# central.net
KiCad netlist of a schematic drawn in EAGLE
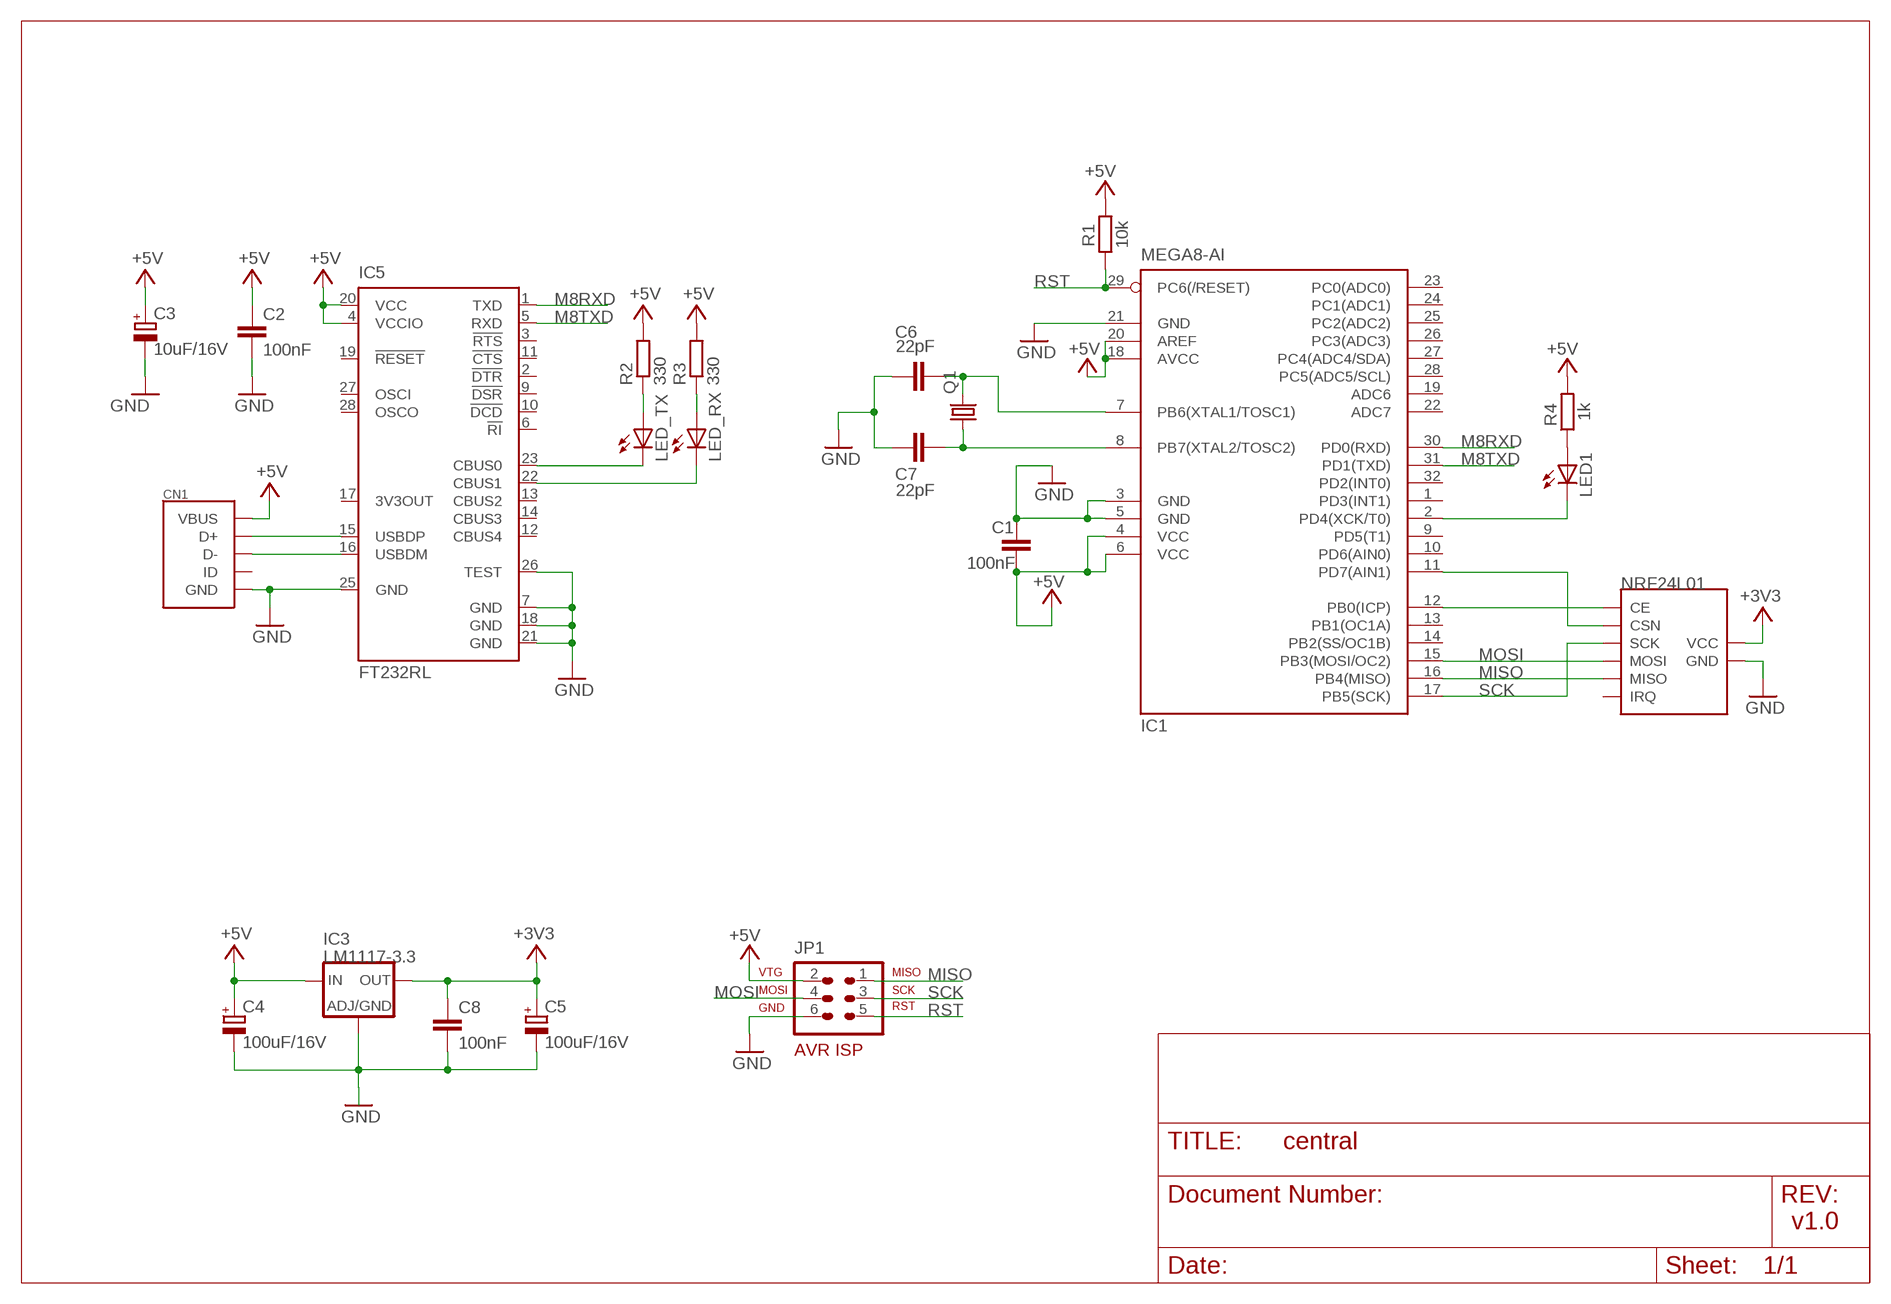
[diagram p0: schematic, sheet 1]

(export (version "E")
  (design (tool "Eeschema 10.0.6"))
  (components
    (comp (ref "C1")
      (value "100nF")
      (footprint "eagle-import:C0805K")
      (libsource (lib "eagle-import") (part "C-EUC0805K"))
    )
    (comp (ref "C2")
      (value "100nF")
      (footprint "eagle-import:C0805K")
      (libsource (lib "eagle-import") (part "C-EUC0805K"))
    )
    (comp (ref "C3")
      (value "10uF/16V")
      (footprint "eagle-import:PANASONIC_D")
      (libsource (lib "eagle-import") (part "CPOL-EUPD"))
    )
    (comp (ref "C4")
      (value "100uF/16V")
      (footprint "eagle-import:PANASONIC_D")
      (libsource (lib "eagle-import") (part "CPOL-EUPD"))
    )
    (comp (ref "C5")
      (value "100uF/16V")
      (footprint "eagle-import:PANASONIC_D")
      (libsource (lib "eagle-import") (part "CPOL-EUPD"))
    )
    (comp (ref "C6")
      (value "22pF")
      (footprint "eagle-import:C0805K")
      (libsource (lib "eagle-import") (part "C-EUC0805K"))
    )
    (comp (ref "C7")
      (value "22pF")
      (footprint "eagle-import:C0805K")
      (libsource (lib "eagle-import") (part "C-EUC0805K"))
    )
    (comp (ref "C8")
      (value "100nF")
      (footprint "eagle-import:C0805K")
      (libsource (lib "eagle-import") (part "C-EUC0805K"))
    )
    (comp (ref "CN1")
      (value "USBMINIB")
      (footprint "eagle-import:USB-MINIB")
      (libsource (lib "eagle-import") (part "USBMINIB"))
    )
    (comp (ref "IC1")
      (value "MEGA8-AI")
      (footprint "eagle-import:TQFP32-08")
      (fields (field (name "MPN") "ATMEGA8-16AU"))
      (libsource (lib "eagle-import") (part "MEGA8-AI"))
    )
    (comp (ref "IC3")
      (value "LM1117-3.3")
      (footprint "eagle-import:SOT223")
      (libsource (lib "eagle-import") (part "LM1117S"))
    )
    (comp (ref "IC4")
      (value "NRF24L01")
      (footprint "eagle-import:NRF24L01-MODULE")
      (libsource (lib "eagle-import") (part "NRF24L01-MODULE"))
    )
    (comp (ref "IC5")
      (value "FT232RL")
      (footprint "eagle-import:SSOP28")
      (libsource (lib "eagle-import") (part "FT232RL"))
    )
    (comp (ref "JP1")
      (value "AVR-ISP-6")
      (footprint "eagle-import:AVR-ISP-6")
      (libsource (lib "eagle-import") (part "AVR-ISP-6"))
    )
    (comp (ref "LED1")
      (value "LED3MM")
      (footprint "eagle-import:LED3MM")
      (libsource (lib "eagle-import") (part "LED3MM"))
    )
    (comp (ref "LED_RX")
      (value "LED0805")
      (footprint "eagle-import:CHIP-LED0805")
      (libsource (lib "eagle-import") (part "LED0805"))
    )
    (comp (ref "LED_TX")
      (value "LED0805")
      (footprint "eagle-import:CHIP-LED0805")
      (libsource (lib "eagle-import") (part "LED0805"))
    )
    (comp (ref "Q1")
      (value "CRYSTALHC49UP")
      (footprint "eagle-import:HC49UP")
      (libsource (lib "eagle-import") (part "CRYSTALHC49UP"))
    )
    (comp (ref "R1")
      (value "10k")
      (footprint "eagle-import:R0805")
      (libsource (lib "eagle-import") (part "R-EU_R0805"))
    )
    (comp (ref "R2")
      (value "330")
      (footprint "eagle-import:R0805")
      (libsource (lib "eagle-import") (part "R-EU_R0805"))
    )
    (comp (ref "R3")
      (value "330")
      (footprint "eagle-import:R0805")
      (libsource (lib "eagle-import") (part "R-EU_R0805"))
    )
    (comp (ref "R4")
      (value "1k")
      (footprint "eagle-import:0207_7")
      (libsource (lib "eagle-import") (part "R-EU_7"))
    )
  )
  (nets
    (net (code "1") (name "+3V3") (class "Default")
      (node (ref "C5") (pin "+") (pinfunction "+_+") (pintype "passive"))
      (node (ref "C8") (pin "1") (pinfunction "1_1") (pintype "passive"))
      (node (ref "IC3") (pin "2") (pinfunction "OUT_2") (pintype "passive"))
      (node (ref "IC3") (pin "4") (pinfunction "OUT_4") (pintype "passive"))
      (node (ref "IC4") (pin "2") (pinfunction "VCC_2") (pintype "power_in"))
    )
    (net (code "2") (name "+5V") (class "Default")
      (node (ref "C1") (pin "2") (pinfunction "2_2") (pintype "passive"))
      (node (ref "C2") (pin "1") (pinfunction "1_1") (pintype "passive"))
      (node (ref "C3") (pin "+") (pinfunction "+_+") (pintype "passive"))
      (node (ref "C4") (pin "+") (pinfunction "+_+") (pintype "passive"))
      (node (ref "CN1") (pin "VBUS") (pinfunction "VBUS_VBUS") (pintype "power_in"))
      (node (ref "IC1") (pin "18") (pinfunction "AVCC_18") (pintype "power_in"))
      (node (ref "IC1") (pin "20") (pinfunction "AREF_20") (pintype "passive"))
      (node (ref "IC1") (pin "4") (pinfunction "VCC_4") (pintype "power_in"))
      (node (ref "IC1") (pin "6") (pinfunction "VCC_6") (pintype "power_in"))
      (node (ref "IC3") (pin "3") (pinfunction "IN_3") (pintype "input"))
      (node (ref "IC5") (pin "20") (pinfunction "VCC_20") (pintype "power_in"))
      (node (ref "IC5") (pin "4") (pinfunction "VCCIO_4") (pintype "power_in"))
      (node (ref "JP1") (pin "2") (pinfunction "VTG_2") (pintype "passive"))
      (node (ref "R1") (pin "2") (pinfunction "2_2") (pintype "passive"))
      (node (ref "R2") (pin "2") (pinfunction "2_2") (pintype "passive"))
      (node (ref "R3") (pin "2") (pinfunction "2_2") (pintype "passive"))
      (node (ref "R4") (pin "2") (pinfunction "2_2") (pintype "passive"))
    )
    (net (code "3") (name "/M8RXD") (class "Default")
      (node (ref "IC1") (pin "30") (pinfunction "PD0(RXD)_30") (pintype "bidirectional"))
      (node (ref "IC5") (pin "1") (pinfunction "TXD_1") (pintype "output"))
    )
    (net (code "4") (name "/M8TXD") (class "Default")
      (node (ref "IC1") (pin "31") (pinfunction "PD1(TXD)_31") (pintype "bidirectional"))
      (node (ref "IC5") (pin "5") (pinfunction "RXD_5") (pintype "input"))
    )
    (net (code "5") (name "/MISO") (class "Default")
      (node (ref "IC1") (pin "16") (pinfunction "PB4(MISO)_16") (pintype "bidirectional"))
      (node (ref "IC4") (pin "7") (pinfunction "MISO_7") (pintype "bidirectional"))
      (node (ref "JP1") (pin "1") (pinfunction "MISO_1") (pintype "passive"))
    )
    (net (code "6") (name "/MOSI") (class "Default")
      (node (ref "IC1") (pin "15") (pinfunction "PB3(MOSI/OC2)_15") (pintype "bidirectional"))
      (node (ref "IC4") (pin "6") (pinfunction "MOSI_6") (pintype "bidirectional"))
      (node (ref "JP1") (pin "4") (pinfunction "MOSI_4") (pintype "passive"))
    )
    (net (code "7") (name "/RST") (class "Default")
      (node (ref "IC1") (pin "29") (pinfunction "PC6(/RESET)_29") (pintype "bidirectional"))
      (node (ref "JP1") (pin "5") (pinfunction "RST_5") (pintype "passive"))
      (node (ref "R1") (pin "1") (pinfunction "1_1") (pintype "passive"))
    )
    (net (code "8") (name "/SCK") (class "Default")
      (node (ref "IC1") (pin "17") (pinfunction "PB5(SCK)_17") (pintype "bidirectional"))
      (node (ref "IC4") (pin "5") (pinfunction "SCK_5") (pintype "bidirectional"))
      (node (ref "JP1") (pin "3") (pinfunction "SCK_3") (pintype "passive"))
    )
    (net (code "9") (name "GND") (class "Default")
      (node (ref "C1") (pin "1") (pinfunction "1_1") (pintype "passive"))
      (node (ref "C2") (pin "2") (pinfunction "2_2") (pintype "passive"))
      (node (ref "C3") (pin "-") (pinfunction "-_-") (pintype "passive"))
      (node (ref "C4") (pin "-") (pinfunction "-_-") (pintype "passive"))
      (node (ref "C5") (pin "-") (pinfunction "-_-") (pintype "passive"))
      (node (ref "C6") (pin "1") (pinfunction "1_1") (pintype "passive"))
      (node (ref "C7") (pin "1") (pinfunction "1_1") (pintype "passive"))
      (node (ref "C8") (pin "2") (pinfunction "2_2") (pintype "passive"))
      (node (ref "CN1") (pin "GND") (pinfunction "GND_GND") (pintype "power_in"))
      (node (ref "IC1") (pin "21") (pinfunction "GND_21") (pintype "power_in"))
      (node (ref "IC1") (pin "3") (pinfunction "GND_3") (pintype "power_in"))
      (node (ref "IC1") (pin "5") (pinfunction "GND_5") (pintype "power_in"))
      (node (ref "IC3") (pin "1") (pinfunction "ADJ_1") (pintype "input"))
      (node (ref "IC4") (pin "1") (pinfunction "GND_1") (pintype "power_in"))
      (node (ref "IC5") (pin "18") (pinfunction "GND_18") (pintype "power_in"))
      (node (ref "IC5") (pin "21") (pinfunction "GND_21") (pintype "power_in"))
      (node (ref "IC5") (pin "25") (pinfunction "GND_25") (pintype "power_in"))
      (node (ref "IC5") (pin "26") (pinfunction "TEST_26") (pintype "input"))
      (node (ref "IC5") (pin "7") (pinfunction "GND_7") (pintype "power_in"))
      (node (ref "JP1") (pin "6") (pinfunction "GND_6") (pintype "passive"))
    )
    (net (code "10") (name "Net-(IC1-PB0(ICP))") (class "Default")
      (node (ref "IC1") (pin "12") (pinfunction "PB0(ICP)_12") (pintype "bidirectional"))
      (node (ref "IC4") (pin "3") (pinfunction "CE_3") (pintype "bidirectional"))
    )
    (net (code "11") (name "Net-(IC1-PB6(XTAL1{slash}TOSC1))") (class "Default")
      (node (ref "C6") (pin "2") (pinfunction "2_2") (pintype "passive"))
      (node (ref "IC1") (pin "7") (pinfunction "PB6(XTAL1/TOSC1)_7") (pintype "bidirectional"))
      (node (ref "Q1") (pin "2") (pinfunction "2_2") (pintype "passive"))
    )
    (net (code "12") (name "Net-(IC1-PB7(XTAL2{slash}TOSC2))") (class "Default")
      (node (ref "C7") (pin "2") (pinfunction "2_2") (pintype "passive"))
      (node (ref "IC1") (pin "8") (pinfunction "PB7(XTAL2/TOSC2)_8") (pintype "bidirectional"))
      (node (ref "Q1") (pin "1") (pinfunction "1_1") (pintype "passive"))
    )
    (net (code "13") (name "Net-(IC1-PD4(XCK{slash}T0))") (class "Default")
      (node (ref "IC1") (pin "2") (pinfunction "PD4(XCK/T0)_2") (pintype "bidirectional"))
      (node (ref "LED1") (pin "K") (pinfunction "C_K") (pintype "passive"))
    )
    (net (code "14") (name "Net-(IC1-PD7(AIN1))") (class "Default")
      (node (ref "IC1") (pin "11") (pinfunction "PD7(AIN1)_11") (pintype "bidirectional"))
      (node (ref "IC4") (pin "4") (pinfunction "CSN_4") (pintype "bidirectional"))
    )
    (net (code "15") (name "Net-(IC5-CBUS0)") (class "Default")
      (node (ref "IC5") (pin "23") (pinfunction "CBUS0_23") (pintype "bidirectional"))
      (node (ref "LED_TX") (pin "C") (pinfunction "C_C") (pintype "passive"))
    )
    (net (code "16") (name "Net-(IC5-CBUS1)") (class "Default")
      (node (ref "IC5") (pin "22") (pinfunction "CBUS1_22") (pintype "bidirectional"))
      (node (ref "LED_RX") (pin "C") (pinfunction "C_C") (pintype "passive"))
    )
    (net (code "17") (name "Net-(IC5-USBDM)") (class "Default")
      (node (ref "CN1") (pin "D-") (pinfunction "D-_D-") (pintype "bidirectional"))
      (node (ref "IC5") (pin "16") (pinfunction "USBDM_16") (pintype "bidirectional"))
    )
    (net (code "18") (name "Net-(IC5-USBDP)") (class "Default")
      (node (ref "CN1") (pin "D+") (pinfunction "D+_D+") (pintype "bidirectional"))
      (node (ref "IC5") (pin "15") (pinfunction "USBDP_15") (pintype "bidirectional"))
    )
    (net (code "19") (name "Net-(LED1-PadA)") (class "Default")
      (node (ref "LED1") (pin "A") (pinfunction "A_A") (pintype "passive"))
      (node (ref "R4") (pin "1") (pinfunction "1_1") (pintype "passive"))
    )
    (net (code "20") (name "Net-(LED_RX-PadA)") (class "Default")
      (node (ref "LED_RX") (pin "A") (pinfunction "A_A") (pintype "passive"))
      (node (ref "R3") (pin "1") (pinfunction "1_1") (pintype "passive"))
    )
    (net (code "21") (name "Net-(LED_TX-PadA)") (class "Default")
      (node (ref "LED_TX") (pin "A") (pinfunction "A_A") (pintype "passive"))
      (node (ref "R2") (pin "1") (pinfunction "1_1") (pintype "passive"))
    )
    (net (code "22") (name "unconnected-(CN1-PadID)") (class "Default")
      (node (ref "CN1") (pin "ID") (pinfunction "ID_ID") (pintype "bidirectional"))
    )
    (net (code "23") (name "unconnected-(IC1-ADC6-Pad19)") (class "Default")
      (node (ref "IC1") (pin "19") (pinfunction "ADC6_19") (pintype "bidirectional"))
    )
    (net (code "24") (name "unconnected-(IC1-ADC7-Pad22)") (class "Default")
      (node (ref "IC1") (pin "22") (pinfunction "ADC7_22") (pintype "bidirectional"))
    )
    (net (code "25") (name "unconnected-(IC1-PB1(OC1A)-Pad13)") (class "Default")
      (node (ref "IC1") (pin "13") (pinfunction "PB1(OC1A)_13") (pintype "bidirectional"))
    )
    (net (code "26") (name "unconnected-(IC1-PB2(SS{slash}OC1B)-Pad14)") (class "Default")
      (node (ref "IC1") (pin "14") (pinfunction "PB2(SS/OC1B)_14") (pintype "bidirectional"))
    )
    (net (code "27") (name "unconnected-(IC1-PC0(ADC0)-Pad23)") (class "Default")
      (node (ref "IC1") (pin "23") (pinfunction "PC0(ADC0)_23") (pintype "bidirectional"))
    )
    (net (code "28") (name "unconnected-(IC1-PC1(ADC1)-Pad24)") (class "Default")
      (node (ref "IC1") (pin "24") (pinfunction "PC1(ADC1)_24") (pintype "bidirectional"))
    )
    (net (code "29") (name "unconnected-(IC1-PC2(ADC2)-Pad25)") (class "Default")
      (node (ref "IC1") (pin "25") (pinfunction "PC2(ADC2)_25") (pintype "bidirectional"))
    )
    (net (code "30") (name "unconnected-(IC1-PC3(ADC3)-Pad26)") (class "Default")
      (node (ref "IC1") (pin "26") (pinfunction "PC3(ADC3)_26") (pintype "bidirectional"))
    )
    (net (code "31") (name "unconnected-(IC1-PC4(ADC4{slash}SDA)-Pad27)") (class "Default")
      (node (ref "IC1") (pin "27") (pinfunction "PC4(ADC4/SDA)_27") (pintype "bidirectional"))
    )
    (net (code "32") (name "unconnected-(IC1-PC5(ADC5{slash}SCL)-Pad28)") (class "Default")
      (node (ref "IC1") (pin "28") (pinfunction "PC5(ADC5/SCL)_28") (pintype "bidirectional"))
    )
    (net (code "33") (name "unconnected-(IC1-PD2(INT0)-Pad32)") (class "Default")
      (node (ref "IC1") (pin "32") (pinfunction "PD2(INT0)_32") (pintype "bidirectional"))
    )
    (net (code "34") (name "unconnected-(IC1-PD3(INT1)-Pad1)") (class "Default")
      (node (ref "IC1") (pin "1") (pinfunction "PD3(INT1)_1") (pintype "bidirectional"))
    )
    (net (code "35") (name "unconnected-(IC1-PD5(T1)-Pad9)") (class "Default")
      (node (ref "IC1") (pin "9") (pinfunction "PD5(T1)_9") (pintype "bidirectional"))
    )
    (net (code "36") (name "unconnected-(IC1-PD6(AIN0)-Pad10)") (class "Default")
      (node (ref "IC1") (pin "10") (pinfunction "PD6(AIN0)_10") (pintype "bidirectional"))
    )
    (net (code "37") (name "unconnected-(IC4-IRQ-Pad8)") (class "Default")
      (node (ref "IC4") (pin "8") (pinfunction "IRQ_8") (pintype "bidirectional"))
    )
    (net (code "38") (name "unconnected-(IC5-3V3OUT-Pad17)") (class "Default")
      (node (ref "IC5") (pin "17") (pinfunction "3V3OUT_17") (pintype "output"))
    )
    (net (code "39") (name "unconnected-(IC5-CBUS2-Pad13)") (class "Default")
      (node (ref "IC5") (pin "13") (pinfunction "CBUS2_13") (pintype "bidirectional"))
    )
    (net (code "40") (name "unconnected-(IC5-CBUS3-Pad14)") (class "Default")
      (node (ref "IC5") (pin "14") (pinfunction "CBUS3_14") (pintype "bidirectional"))
    )
    (net (code "41") (name "unconnected-(IC5-CBUS4-Pad12)") (class "Default")
      (node (ref "IC5") (pin "12") (pinfunction "CBUS4_12") (pintype "bidirectional"))
    )
    (net (code "42") (name "unconnected-(IC5-OSCI-Pad27)") (class "Default")
      (node (ref "IC5") (pin "27") (pinfunction "OSCI_27") (pintype "input"))
    )
    (net (code "43") (name "unconnected-(IC5-OSCO-Pad28)") (class "Default")
      (node (ref "IC5") (pin "28") (pinfunction "OSCO_28") (pintype "output"))
    )
    (net (code "44") (name "unconnected-(IC5-~{CTS}-Pad11)") (class "Default")
      (node (ref "IC5") (pin "11") (pinfunction "~{CTS}_11") (pintype "input"))
    )
    (net (code "45") (name "unconnected-(IC5-~{DCD}-Pad10)") (class "Default")
      (node (ref "IC5") (pin "10") (pinfunction "~{DCD}_10") (pintype "input"))
    )
    (net (code "46") (name "unconnected-(IC5-~{DSR}-Pad9)") (class "Default")
      (node (ref "IC5") (pin "9") (pinfunction "~{DSR}_9") (pintype "input"))
    )
    (net (code "47") (name "unconnected-(IC5-~{DTR}-Pad2)") (class "Default")
      (node (ref "IC5") (pin "2") (pinfunction "~{DTR}_2") (pintype "output"))
    )
    (net (code "48") (name "unconnected-(IC5-~{RESET}-Pad19)") (class "Default")
      (node (ref "IC5") (pin "19") (pinfunction "~{RESET}_19") (pintype "input"))
    )
    (net (code "49") (name "unconnected-(IC5-~{RI}-Pad6)") (class "Default")
      (node (ref "IC5") (pin "6") (pinfunction "~{RI}_6") (pintype "input"))
    )
    (net (code "50") (name "unconnected-(IC5-~{RTS}-Pad3)") (class "Default")
      (node (ref "IC5") (pin "3") (pinfunction "~{RTS}_3") (pintype "output"))
    )
  )
)
